# temperature.net
KiCad netlist of a schematic drawn in EAGLE
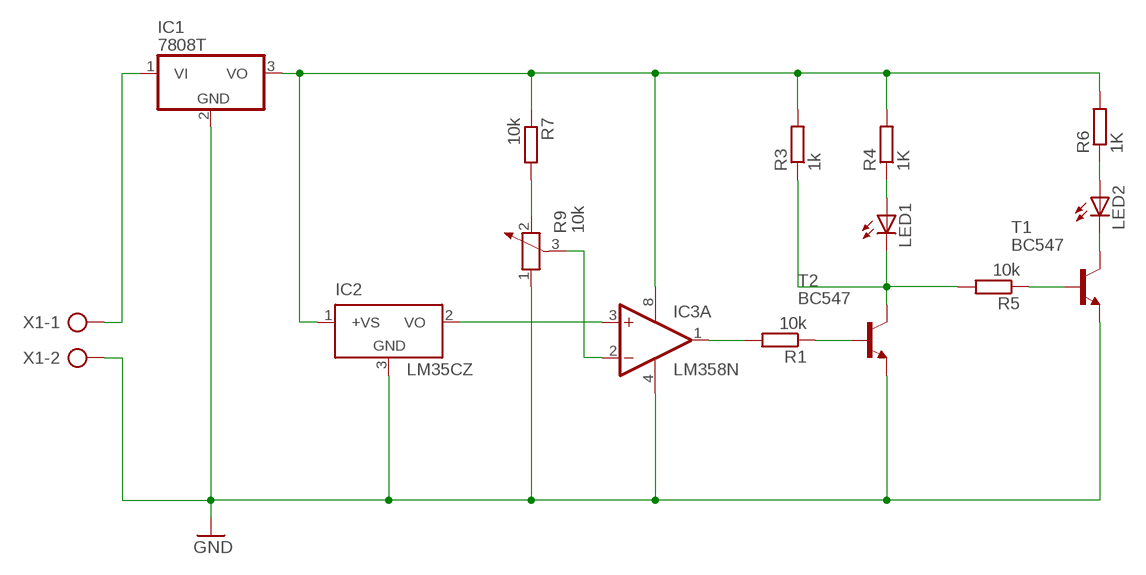
[diagram p0: schematic, sheet 1]

(export (version "E")
  (design (tool "Eeschema 10.0.6"))
  (components
    (comp (ref "IC1")
      (value "7808T")
      (footprint "eagle-import:TO220H")
      (libsource (lib "eagle-import") (part "78T08"))
    )
    (comp (ref "IC2")
      (value "LM35CZ")
      (footprint "eagle-import:TO92")
      (libsource (lib "eagle-import") (part "LM35CZ"))
    )
    (comp (ref "IC3")
      (value "LM358N")
      (footprint "eagle-import:DIL08")
      (libsource (lib "eagle-import") (part "LM358N"))
    )
    (comp (ref "LED1")
      (value "LED5MM")
      (footprint "eagle-import:LED5MM")
      (libsource (lib "eagle-import") (part "LED5MM"))
    )
    (comp (ref "LED2")
      (value "LED5MM")
      (footprint "eagle-import:LED5MM")
      (libsource (lib "eagle-import") (part "LED5MM"))
    )
    (comp (ref "R1")
      (value "10k")
      (footprint "eagle-import:0204_7")
      (libsource (lib "eagle-import") (part "R-EU_0204/7"))
    )
    (comp (ref "R3")
      (value "1k")
      (footprint "eagle-import:0204_7")
      (libsource (lib "eagle-import") (part "R-EU_0204/7"))
    )
    (comp (ref "R4")
      (value "1K")
      (footprint "eagle-import:0204_7")
      (libsource (lib "eagle-import") (part "R-EU_0204/7"))
    )
    (comp (ref "R5")
      (value "10k")
      (footprint "eagle-import:0204_7")
      (libsource (lib "eagle-import") (part "R-EU_0204/7"))
    )
    (comp (ref "R6")
      (value "1K")
      (footprint "eagle-import:0204_7")
      (libsource (lib "eagle-import") (part "R-EU_0204/7"))
    )
    (comp (ref "R7")
      (value "10k")
      (footprint "eagle-import:0204_7")
      (libsource (lib "eagle-import") (part "R-EU_0204/7"))
    )
    (comp (ref "R9")
      (value "10k")
      (footprint "eagle-import:PT-10")
      (libsource (lib "eagle-import") (part "POTENTIOMETER_PT-10"))
    )
    (comp (ref "T1")
      (value "BC547")
      (footprint "eagle-import:TO92")
      (libsource (lib "eagle-import") (part "BC547"))
    )
    (comp (ref "T2")
      (value "BC547")
      (footprint "eagle-import:TO92")
      (libsource (lib "eagle-import") (part "BC547"))
    )
    (comp (ref "X1")
      (value "AK300/2")
      (footprint "eagle-import:AK300_2")
      (libsource (lib "eagle-import") (part "AK300/2"))
    )
  )
  (nets
    (net (code "1") (name "GND") (class "Default")
      (node (ref "IC1") (pin "2") (pinfunction "GND_2") (pintype "passive"))
      (node (ref "IC2") (pin "3") (pinfunction "GND_3") (pintype "power_in"))
      (node (ref "IC3") (pin "4") (pinfunction "V-_4") (pintype "power_in"))
      (node (ref "R9") (pin "1") (pinfunction "1_1") (pintype "passive"))
      (node (ref "T1") (pin "1") (pinfunction "E_1") (pintype "passive"))
      (node (ref "T2") (pin "1") (pinfunction "E_1") (pintype "passive"))
      (node (ref "X1") (pin "2") (pinfunction "KL_2") (pintype "passive"))
    )
    (net (code "2") (name "Net-(IC1-VI)") (class "Default")
      (node (ref "IC1") (pin "1") (pinfunction "VI_1") (pintype "input"))
      (node (ref "X1") (pin "1") (pinfunction "KL_1") (pintype "passive"))
    )
    (net (code "3") (name "Net-(IC1-VO)") (class "Default")
      (node (ref "IC1") (pin "3") (pinfunction "VO_3") (pintype "passive"))
      (node (ref "IC2") (pin "1") (pinfunction "+VS_1") (pintype "input"))
      (node (ref "IC3") (pin "8") (pinfunction "V+_8") (pintype "power_in"))
      (node (ref "R3") (pin "2") (pinfunction "2_2") (pintype "passive"))
      (node (ref "R4") (pin "2") (pinfunction "2_2") (pintype "passive"))
      (node (ref "R6") (pin "2") (pinfunction "2_2") (pintype "passive"))
      (node (ref "R7") (pin "1") (pinfunction "1_1") (pintype "passive"))
    )
    (net (code "4") (name "Net-(IC2-VO)") (class "Default")
      (node (ref "IC2") (pin "2") (pinfunction "VO_2") (pintype "input"))
      (node (ref "IC3") (pin "3") (pinfunction "+IN_3") (pintype "input"))
    )
    (net (code "5") (name "Net-(IC3A--IN)") (class "Default")
      (node (ref "IC3") (pin "2") (pinfunction "-IN_2") (pintype "input"))
      (node (ref "R9") (pin "3") (pinfunction "3_3") (pintype "passive"))
    )
    (net (code "6") (name "Net-(IC3A-OUT)") (class "Default")
      (node (ref "IC3") (pin "1") (pinfunction "OUT_1") (pintype "output"))
      (node (ref "R1") (pin "2") (pinfunction "2_2") (pintype "passive"))
    )
    (net (code "7") (name "Net-(LED1-C)") (class "Default")
      (node (ref "LED1") (pin "K") (pinfunction "C_K") (pintype "passive"))
      (node (ref "R3") (pin "1") (pinfunction "1_1") (pintype "passive"))
      (node (ref "R5") (pin "2") (pinfunction "2_2") (pintype "passive"))
      (node (ref "T2") (pin "3") (pinfunction "C_3") (pintype "passive"))
    )
    (net (code "8") (name "Net-(LED1-PadA)") (class "Default")
      (node (ref "LED1") (pin "A") (pinfunction "A_A") (pintype "passive"))
      (node (ref "R4") (pin "1") (pinfunction "1_1") (pintype "passive"))
    )
    (net (code "9") (name "Net-(LED2-C)") (class "Default")
      (node (ref "LED2") (pin "K") (pinfunction "C_K") (pintype "passive"))
      (node (ref "T1") (pin "3") (pinfunction "C_3") (pintype "passive"))
    )
    (net (code "10") (name "Net-(LED2-PadA)") (class "Default")
      (node (ref "LED2") (pin "A") (pinfunction "A_A") (pintype "passive"))
      (node (ref "R6") (pin "1") (pinfunction "1_1") (pintype "passive"))
    )
    (net (code "11") (name "Net-(R7-Pad2)") (class "Default")
      (node (ref "R7") (pin "2") (pinfunction "2_2") (pintype "passive"))
      (node (ref "R9") (pin "2") (pinfunction "2_2") (pintype "passive"))
    )
    (net (code "12") (name "Net-(T1-B)") (class "Default")
      (node (ref "R5") (pin "1") (pinfunction "1_1") (pintype "passive"))
      (node (ref "T1") (pin "2") (pinfunction "B_2") (pintype "passive"))
    )
    (net (code "13") (name "Net-(T2-B)") (class "Default")
      (node (ref "R1") (pin "1") (pinfunction "1_1") (pintype "passive"))
      (node (ref "T2") (pin "2") (pinfunction "B_2") (pintype "passive"))
    )
  )
)
